# Key_Reset.net
KiCad netlist of a schematic drawn in Altium Designer
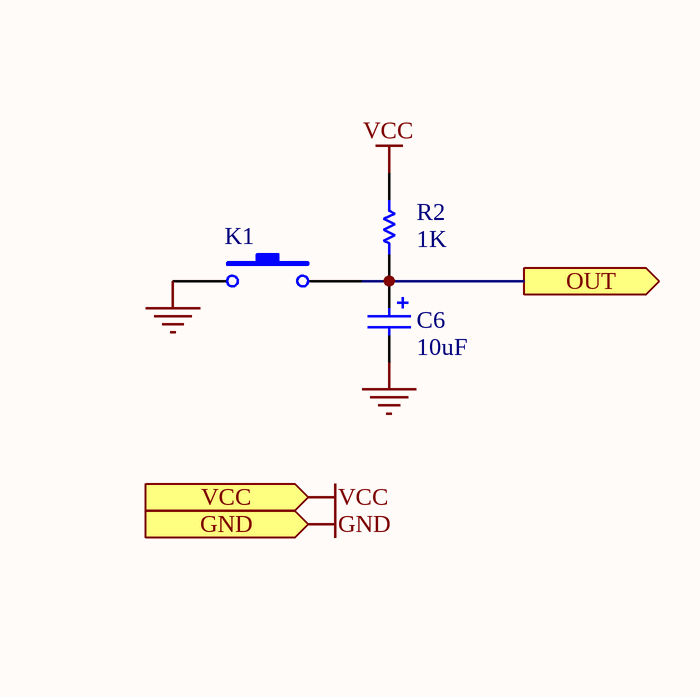
[diagram p0: Key_Reset.SchDoc]

(export (version "E")
  (design (tool "Eeschema 10.0.6"))
  (components
    (comp (ref "C6")
      (value "10uF")
      (footprint "CAPPR2.5-6.3x5")
      (description "Polarized Capacitor (Radial)")
      (fields
        (field (name "MANUFACTURER") "Generic Components")
        (field (name "Comment") "Capacitor")
        (field (name "PUBLISHER") "Altium Limited")
      )
      (libsource (lib "Miscellaneous Devices") (part "Cap Pol1"))
    )
    (comp (ref "K1")
      (value "SW-PB")
      (footprint "SPST-2_2")
      (description "Switch")
      (fields (field (name "MANUFACTURER") "Generic Components") (field (name "PUBLISHER") "Altium Limited"))
      (libsource (lib "Miscellaneous Devices") (part "SW-PB"))
    )
    (comp (ref "R2")
      (value "1K")
      (footprint "AXIAL-0.4")
      (description "Resistor")
      (fields
        (field (name "MANUFACTURER") "Generic Components")
        (field (name "Comment") "Res1")
        (field (name "PUBLISHER") "Altium Limited")
      )
      (libsource (lib "Miscellaneous Devices") (part "Res1"))
    )
  )
  (nets
    (net (code "1") (name "/OUT") (class "Default")
      (node (ref "C6") (pin "1") (pinfunction "1_1") (pintype "passive"))
      (node (ref "K1") (pin "2") (pinfunction "2_2") (pintype "passive"))
      (node (ref "R2") (pin "2") (pinfunction "2_2") (pintype "passive"))
    )
    (net (code "2") (name "GND") (class "Default")
      (node (ref "C6") (pin "2") (pinfunction "2_2") (pintype "passive"))
      (node (ref "K1") (pin "1") (pinfunction "1_1") (pintype "passive"))
    )
    (net (code "3") (name "VCC") (class "Default")
      (node (ref "R2") (pin "1") (pinfunction "1_1") (pintype "passive"))
    )
  )
)
